# remote.net
KiCad netlist of a schematic drawn in EAGLE
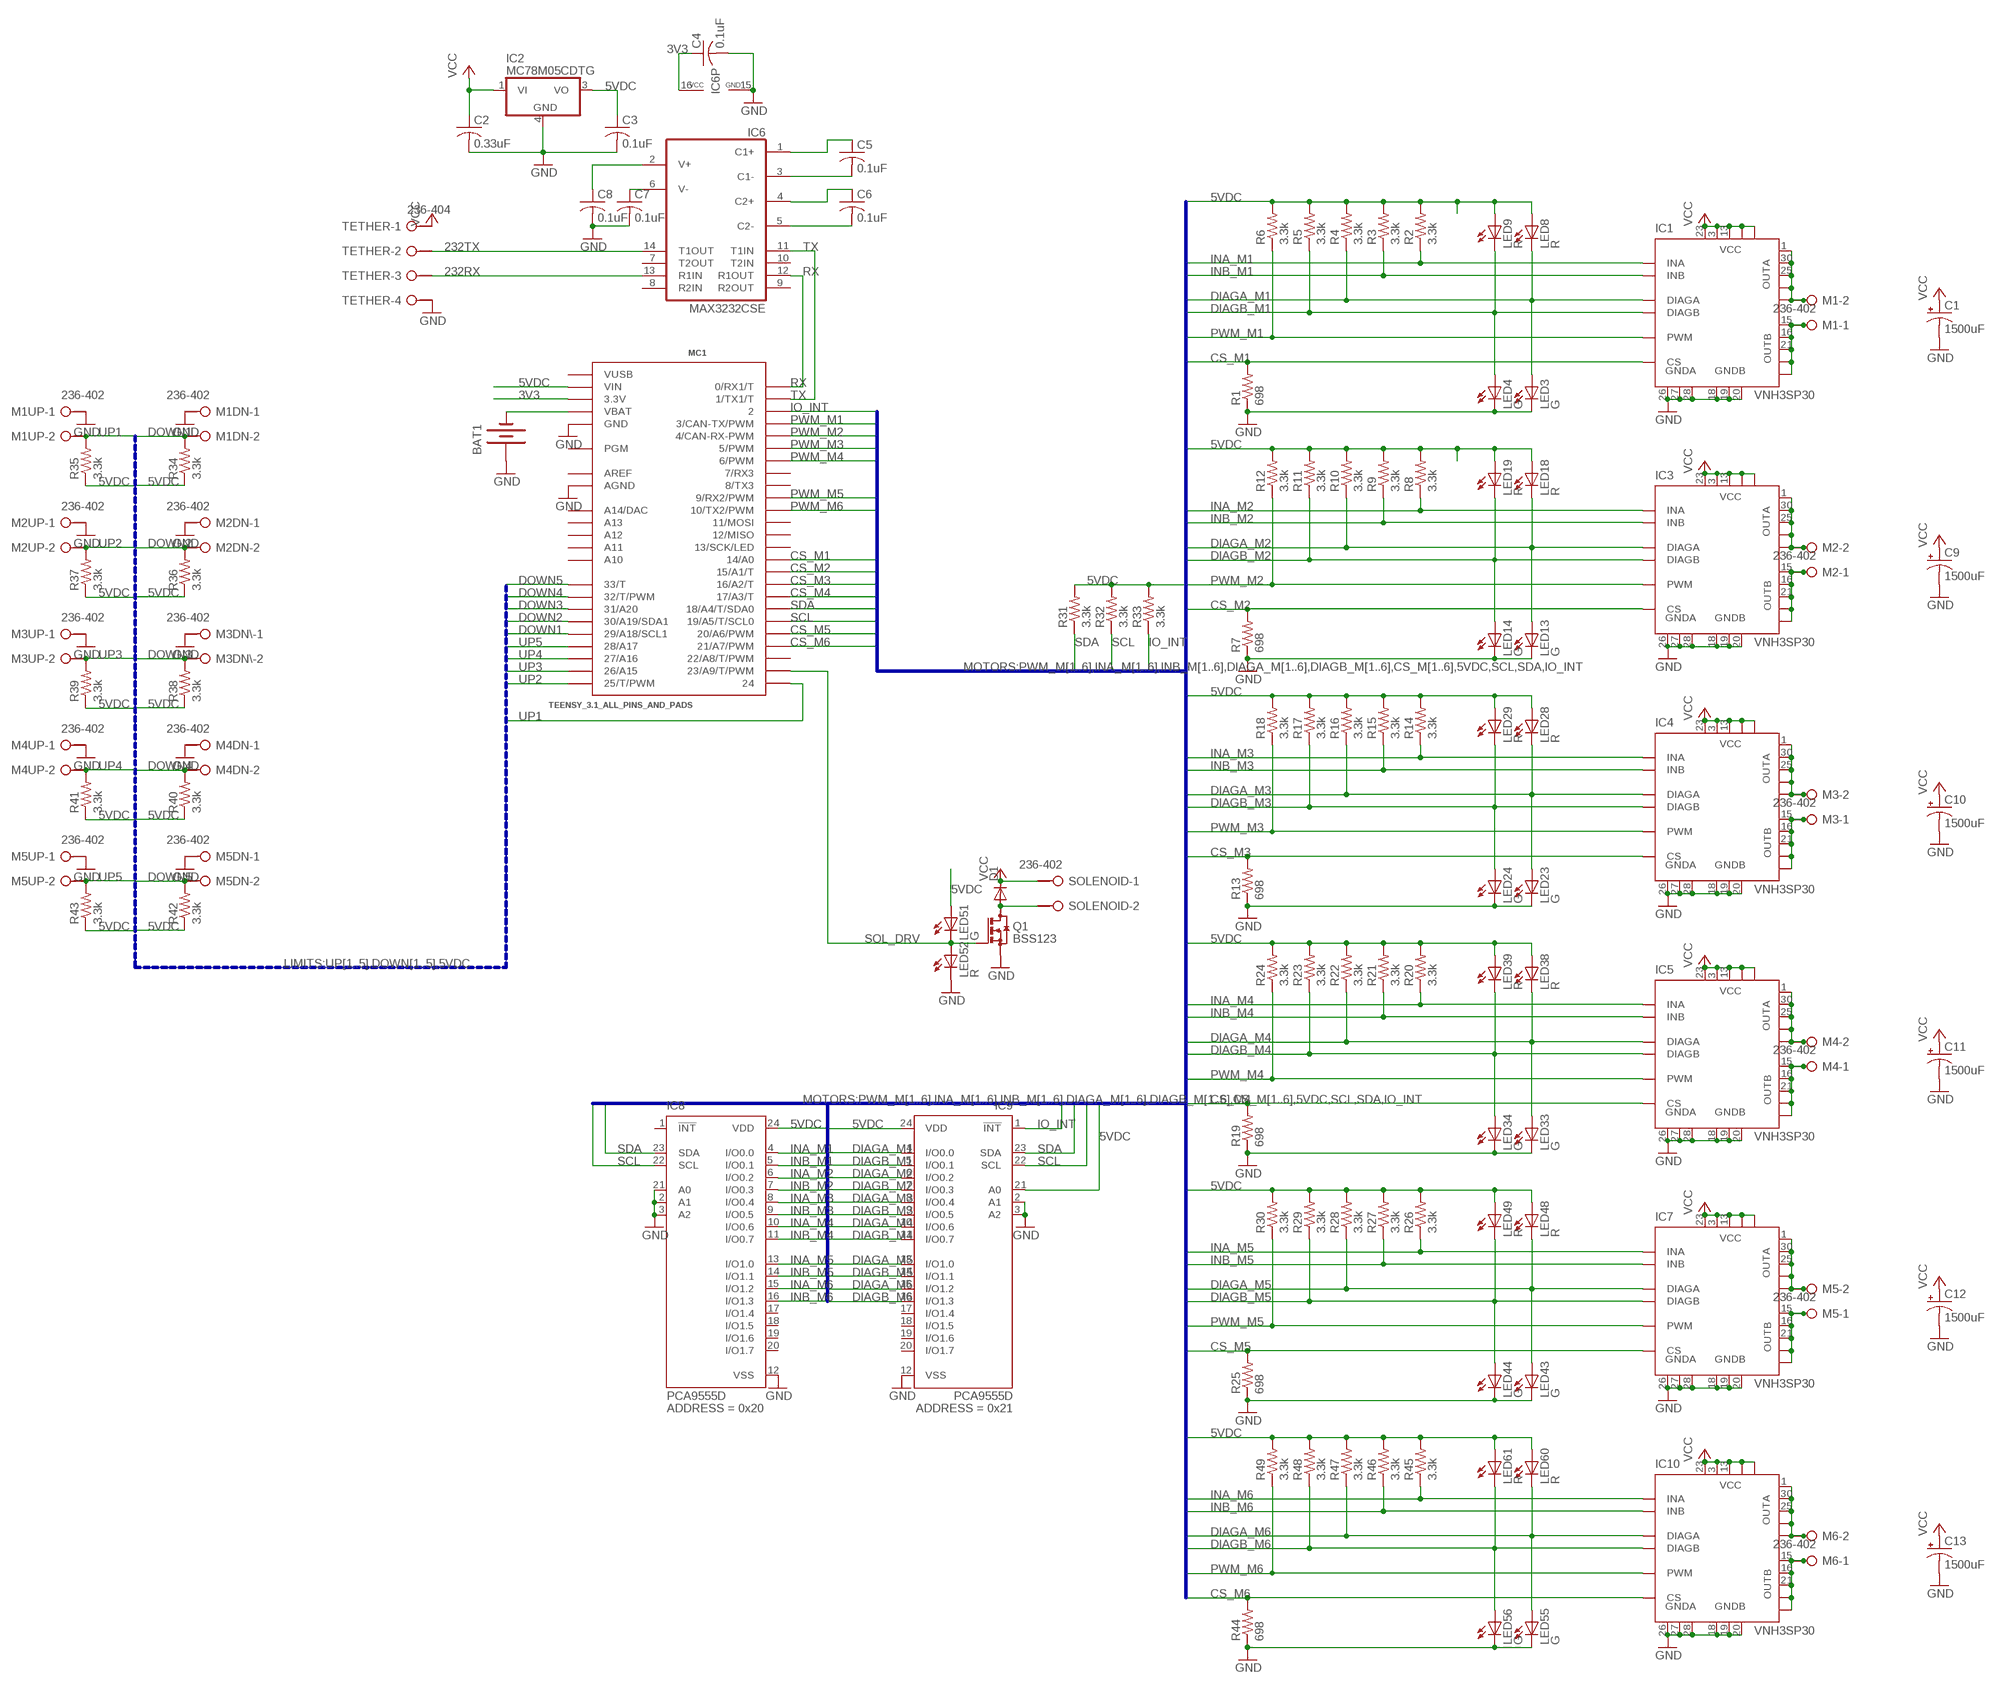
[diagram p0: schematic, sheet 1]

(export (version "E")
  (design (tool "Eeschema 10.0.6"))
  (components
    (comp (ref "BAT1")
      (value "BATTERY20SMD")
      (footprint "eagle-import:BATTCON_20MM")
      (libsource (lib "eagle-import") (part "BATTERY20SMD"))
    )
    (comp (ref "C1")
      (value "1500uF")
      (footprint "eagle-import:SANYO-OSCON_SMD_F12")
      (libsource (lib "eagle-import") (part "CPOL-USSANYO_SMD_F12"))
    )
    (comp (ref "C2")
      (value "0.33uF")
      (footprint "eagle-import:C0805")
      (libsource (lib "eagle-import") (part "C-USC0805"))
    )
    (comp (ref "C3")
      (value "0.1uF")
      (footprint "eagle-import:C0805")
      (libsource (lib "eagle-import") (part "C-USC0805"))
    )
    (comp (ref "C4")
      (value "0.1uF")
      (footprint "eagle-import:C0805")
      (libsource (lib "eagle-import") (part "C-USC0805"))
    )
    (comp (ref "C5")
      (value "0.1uF")
      (footprint "eagle-import:C0805")
      (libsource (lib "eagle-import") (part "C-USC0805"))
    )
    (comp (ref "C6")
      (value "0.1uF")
      (footprint "eagle-import:C0805")
      (libsource (lib "eagle-import") (part "C-USC0805"))
    )
    (comp (ref "C7")
      (value "0.1uF")
      (footprint "eagle-import:C0805")
      (libsource (lib "eagle-import") (part "C-USC0805"))
    )
    (comp (ref "C8")
      (value "0.1uF")
      (footprint "eagle-import:C0805")
      (libsource (lib "eagle-import") (part "C-USC0805"))
    )
    (comp (ref "C9")
      (value "1500uF")
      (footprint "eagle-import:SANYO-OSCON_SMD_F12")
      (libsource (lib "eagle-import") (part "CPOL-USSANYO_SMD_F12"))
    )
    (comp (ref "C10")
      (value "1500uF")
      (footprint "eagle-import:SANYO-OSCON_SMD_F12")
      (libsource (lib "eagle-import") (part "CPOL-USSANYO_SMD_F12"))
    )
    (comp (ref "C11")
      (value "1500uF")
      (footprint "eagle-import:SANYO-OSCON_SMD_F12")
      (libsource (lib "eagle-import") (part "CPOL-USSANYO_SMD_F12"))
    )
    (comp (ref "C12")
      (value "1500uF")
      (footprint "eagle-import:SANYO-OSCON_SMD_F12")
      (libsource (lib "eagle-import") (part "CPOL-USSANYO_SMD_F12"))
    )
    (comp (ref "C13")
      (value "1500uF")
      (footprint "eagle-import:SANYO-OSCON_SMD_F12")
      (libsource (lib "eagle-import") (part "CPOL-USSANYO_SMD_F12"))
    )
    (comp (ref "D1")
      (value "DIODE-DO214AA")
      (footprint "eagle-import:DO214AA")
      (libsource (lib "eagle-import") (part "DIODE-DO214AA"))
    )
    (comp (ref "IC1")
      (value "VNH3SP30")
      (footprint "eagle-import:MULTIPOWERSO-30")
      (fields (field (name "MPN") "VNH3SP30-E"))
      (libsource (lib "eagle-import") (part "VNH3SP30"))
    )
    (comp (ref "IC2")
      (value "MC78M05CDTG")
      (footprint "eagle-import:DPACK_3")
      (libsource (lib "eagle-import") (part "MC78M05CDTG"))
    )
    (comp (ref "IC3")
      (value "VNH3SP30")
      (footprint "eagle-import:MULTIPOWERSO-30")
      (fields (field (name "MPN") "VNH3SP30-E"))
      (libsource (lib "eagle-import") (part "VNH3SP30"))
    )
    (comp (ref "IC4")
      (value "VNH3SP30")
      (footprint "eagle-import:MULTIPOWERSO-30")
      (fields (field (name "MPN") "VNH3SP30-E"))
      (libsource (lib "eagle-import") (part "VNH3SP30"))
    )
    (comp (ref "IC5")
      (value "VNH3SP30")
      (footprint "eagle-import:MULTIPOWERSO-30")
      (fields (field (name "MPN") "VNH3SP30-E"))
      (libsource (lib "eagle-import") (part "VNH3SP30"))
    )
    (comp (ref "IC6")
      (value "MAX3232CSE")
      (footprint "eagle-import:SO16")
      (libsource (lib "eagle-import") (part "MAX3232SEC"))
    )
    (comp (ref "IC7")
      (value "VNH3SP30")
      (footprint "eagle-import:MULTIPOWERSO-30")
      (fields (field (name "MPN") "VNH3SP30-E"))
      (libsource (lib "eagle-import") (part "VNH3SP30"))
    )
    (comp (ref "IC8")
      (value "PCA9555D")
      (footprint "eagle-import:SO24")
      (fields (field (name "MPN") "PCA9555DW") (field (name "ADDRESS") "0x20"))
      (libsource (lib "eagle-import") (part "PCA9555D"))
    )
    (comp (ref "IC9")
      (value "PCA9555D")
      (footprint "eagle-import:SO24")
      (fields (field (name "MPN") "PCA9555DW") (field (name "ADDRESS") "0x21"))
      (libsource (lib "eagle-import") (part "PCA9555D"))
    )
    (comp (ref "IC10")
      (value "VNH3SP30")
      (footprint "eagle-import:MULTIPOWERSO-30")
      (fields (field (name "MPN") "VNH3SP30-E"))
      (libsource (lib "eagle-import") (part "VNH3SP30"))
    )
    (comp (ref "LED3")
      (value "G")
      (footprint "eagle-import:CHIP-LED0805")
      (libsource (lib "eagle-import") (part "LEDCHIP-LED0805"))
    )
    (comp (ref "LED4")
      (value "G")
      (footprint "eagle-import:CHIP-LED0805")
      (libsource (lib "eagle-import") (part "LEDCHIP-LED0805"))
    )
    (comp (ref "LED8")
      (value "R")
      (footprint "eagle-import:CHIP-LED0805")
      (libsource (lib "eagle-import") (part "LEDCHIP-LED0805"))
    )
    (comp (ref "LED9")
      (value "R")
      (footprint "eagle-import:CHIP-LED0805")
      (libsource (lib "eagle-import") (part "LEDCHIP-LED0805"))
    )
    (comp (ref "LED13")
      (value "G")
      (footprint "eagle-import:CHIP-LED0805")
      (libsource (lib "eagle-import") (part "LEDCHIP-LED0805"))
    )
    (comp (ref "LED14")
      (value "G")
      (footprint "eagle-import:CHIP-LED0805")
      (libsource (lib "eagle-import") (part "LEDCHIP-LED0805"))
    )
    (comp (ref "LED18")
      (value "R")
      (footprint "eagle-import:CHIP-LED0805")
      (libsource (lib "eagle-import") (part "LEDCHIP-LED0805"))
    )
    (comp (ref "LED19")
      (value "R")
      (footprint "eagle-import:CHIP-LED0805")
      (libsource (lib "eagle-import") (part "LEDCHIP-LED0805"))
    )
    (comp (ref "LED23")
      (value "G")
      (footprint "eagle-import:CHIP-LED0805")
      (libsource (lib "eagle-import") (part "LEDCHIP-LED0805"))
    )
    (comp (ref "LED24")
      (value "G")
      (footprint "eagle-import:CHIP-LED0805")
      (libsource (lib "eagle-import") (part "LEDCHIP-LED0805"))
    )
    (comp (ref "LED28")
      (value "R")
      (footprint "eagle-import:CHIP-LED0805")
      (libsource (lib "eagle-import") (part "LEDCHIP-LED0805"))
    )
    (comp (ref "LED29")
      (value "R")
      (footprint "eagle-import:CHIP-LED0805")
      (libsource (lib "eagle-import") (part "LEDCHIP-LED0805"))
    )
    (comp (ref "LED33")
      (value "G")
      (footprint "eagle-import:CHIP-LED0805")
      (libsource (lib "eagle-import") (part "LEDCHIP-LED0805"))
    )
    (comp (ref "LED34")
      (value "G")
      (footprint "eagle-import:CHIP-LED0805")
      (libsource (lib "eagle-import") (part "LEDCHIP-LED0805"))
    )
    (comp (ref "LED38")
      (value "R")
      (footprint "eagle-import:CHIP-LED0805")
      (libsource (lib "eagle-import") (part "LEDCHIP-LED0805"))
    )
    (comp (ref "LED39")
      (value "R")
      (footprint "eagle-import:CHIP-LED0805")
      (libsource (lib "eagle-import") (part "LEDCHIP-LED0805"))
    )
    (comp (ref "LED43")
      (value "G")
      (footprint "eagle-import:CHIP-LED0805")
      (libsource (lib "eagle-import") (part "LEDCHIP-LED0805"))
    )
    (comp (ref "LED44")
      (value "G")
      (footprint "eagle-import:CHIP-LED0805")
      (libsource (lib "eagle-import") (part "LEDCHIP-LED0805"))
    )
    (comp (ref "LED48")
      (value "R")
      (footprint "eagle-import:CHIP-LED0805")
      (libsource (lib "eagle-import") (part "LEDCHIP-LED0805"))
    )
    (comp (ref "LED49")
      (value "R")
      (footprint "eagle-import:CHIP-LED0805")
      (libsource (lib "eagle-import") (part "LEDCHIP-LED0805"))
    )
    (comp (ref "LED51")
      (value "G")
      (footprint "eagle-import:CHIP-LED0805")
      (libsource (lib "eagle-import") (part "LEDCHIP-LED0805"))
    )
    (comp (ref "LED52")
      (value "R")
      (footprint "eagle-import:CHIP-LED0805")
      (libsource (lib "eagle-import") (part "LEDCHIP-LED0805"))
    )
    (comp (ref "LED55")
      (value "G")
      (footprint "eagle-import:CHIP-LED0805")
      (libsource (lib "eagle-import") (part "LEDCHIP-LED0805"))
    )
    (comp (ref "LED56")
      (value "G")
      (footprint "eagle-import:CHIP-LED0805")
      (libsource (lib "eagle-import") (part "LEDCHIP-LED0805"))
    )
    (comp (ref "LED60")
      (value "R")
      (footprint "eagle-import:CHIP-LED0805")
      (libsource (lib "eagle-import") (part "LEDCHIP-LED0805"))
    )
    (comp (ref "LED61")
      (value "R")
      (footprint "eagle-import:CHIP-LED0805")
      (libsource (lib "eagle-import") (part "LEDCHIP-LED0805"))
    )
    (comp (ref "M1")
      (value "236-402")
      (footprint "eagle-import:236-402")
      (libsource (lib "eagle-import") (part "236-402"))
    )
    (comp (ref "M1DN")
      (value "236-402")
      (footprint "eagle-import:236-402")
      (libsource (lib "eagle-import") (part "236-402"))
    )
    (comp (ref "M1UP")
      (value "236-402")
      (footprint "eagle-import:236-402")
      (libsource (lib "eagle-import") (part "236-402"))
    )
    (comp (ref "M2")
      (value "236-402")
      (footprint "eagle-import:236-402")
      (libsource (lib "eagle-import") (part "236-402"))
    )
    (comp (ref "M2DN")
      (value "236-402")
      (footprint "eagle-import:236-402")
      (libsource (lib "eagle-import") (part "236-402"))
    )
    (comp (ref "M2UP")
      (value "236-402")
      (footprint "eagle-import:236-402")
      (libsource (lib "eagle-import") (part "236-402"))
    )
    (comp (ref "M3")
      (value "236-402")
      (footprint "eagle-import:236-402")
      (libsource (lib "eagle-import") (part "236-402"))
    )
    (comp (ref "M3DN\\")
      (value "236-402")
      (footprint "eagle-import:236-402")
      (libsource (lib "eagle-import") (part "236-402"))
    )
    (comp (ref "M3UP")
      (value "236-402")
      (footprint "eagle-import:236-402")
      (libsource (lib "eagle-import") (part "236-402"))
    )
    (comp (ref "M4")
      (value "236-402")
      (footprint "eagle-import:236-402")
      (libsource (lib "eagle-import") (part "236-402"))
    )
    (comp (ref "M4DN")
      (value "236-402")
      (footprint "eagle-import:236-402")
      (libsource (lib "eagle-import") (part "236-402"))
    )
    (comp (ref "M4UP")
      (value "236-402")
      (footprint "eagle-import:236-402")
      (libsource (lib "eagle-import") (part "236-402"))
    )
    (comp (ref "M5")
      (value "236-402")
      (footprint "eagle-import:236-402")
      (libsource (lib "eagle-import") (part "236-402"))
    )
    (comp (ref "M5DN")
      (value "236-402")
      (footprint "eagle-import:236-402")
      (libsource (lib "eagle-import") (part "236-402"))
    )
    (comp (ref "M5UP")
      (value "236-402")
      (footprint "eagle-import:236-402")
      (libsource (lib "eagle-import") (part "236-402"))
    )
    (comp (ref "M6")
      (value "236-402")
      (footprint "eagle-import:236-402")
      (libsource (lib "eagle-import") (part "236-402"))
    )
    (comp (ref "MC1")
      (value "TEENSY_3.1_ALL_PINS_AND_PADS")
      (footprint "eagle-import:TEENSY3_ALL_PINS_&_PADS")
      (libsource (lib "eagle-import") (part "TEENSY_3.1_ALL_PINS_AND_PADS"))
    )
    (comp (ref "Q1")
      (value "BSS123")
      (footprint "eagle-import:SOT23")
      (libsource (lib "eagle-import") (part "BSS123"))
    )
    (comp (ref "R1")
      (value "698")
      (footprint "eagle-import:R0805")
      (libsource (lib "eagle-import") (part "R-US_R0805"))
    )
    (comp (ref "R2")
      (value "3.3k")
      (footprint "eagle-import:R0805")
      (libsource (lib "eagle-import") (part "R-US_R0805"))
    )
    (comp (ref "R3")
      (value "3.3k")
      (footprint "eagle-import:R0805")
      (libsource (lib "eagle-import") (part "R-US_R0805"))
    )
    (comp (ref "R4")
      (value "3.3k")
      (footprint "eagle-import:R0805")
      (libsource (lib "eagle-import") (part "R-US_R0805"))
    )
    (comp (ref "R5")
      (value "3.3k")
      (footprint "eagle-import:R0805")
      (libsource (lib "eagle-import") (part "R-US_R0805"))
    )
    (comp (ref "R6")
      (value "3.3k")
      (footprint "eagle-import:R0805")
      (libsource (lib "eagle-import") (part "R-US_R0805"))
    )
    (comp (ref "R7")
      (value "698")
      (footprint "eagle-import:R0805")
      (libsource (lib "eagle-import") (part "R-US_R0805"))
    )
    (comp (ref "R8")
      (value "3.3k")
      (footprint "eagle-import:R0805")
      (libsource (lib "eagle-import") (part "R-US_R0805"))
    )
    (comp (ref "R9")
      (value "3.3k")
      (footprint "eagle-import:R0805")
      (libsource (lib "eagle-import") (part "R-US_R0805"))
    )
    (comp (ref "R10")
      (value "3.3k")
      (footprint "eagle-import:R0805")
      (libsource (lib "eagle-import") (part "R-US_R0805"))
    )
    (comp (ref "R11")
      (value "3.3k")
      (footprint "eagle-import:R0805")
      (libsource (lib "eagle-import") (part "R-US_R0805"))
    )
    (comp (ref "R12")
      (value "3.3k")
      (footprint "eagle-import:R0805")
      (libsource (lib "eagle-import") (part "R-US_R0805"))
    )
    (comp (ref "R13")
      (value "698")
      (footprint "eagle-import:R0805")
      (libsource (lib "eagle-import") (part "R-US_R0805"))
    )
    (comp (ref "R14")
      (value "3.3k")
      (footprint "eagle-import:R0805")
      (libsource (lib "eagle-import") (part "R-US_R0805"))
    )
    (comp (ref "R15")
      (value "3.3k")
      (footprint "eagle-import:R0805")
      (libsource (lib "eagle-import") (part "R-US_R0805"))
    )
    (comp (ref "R16")
      (value "3.3k")
      (footprint "eagle-import:R0805")
      (libsource (lib "eagle-import") (part "R-US_R0805"))
    )
    (comp (ref "R17")
      (value "3.3k")
      (footprint "eagle-import:R0805")
      (libsource (lib "eagle-import") (part "R-US_R0805"))
    )
    (comp (ref "R18")
      (value "3.3k")
      (footprint "eagle-import:R0805")
      (libsource (lib "eagle-import") (part "R-US_R0805"))
    )
    (comp (ref "R19")
      (value "698")
      (footprint "eagle-import:R0805")
      (libsource (lib "eagle-import") (part "R-US_R0805"))
    )
    (comp (ref "R20")
      (value "3.3k")
      (footprint "eagle-import:R0805")
      (libsource (lib "eagle-import") (part "R-US_R0805"))
    )
    (comp (ref "R21")
      (value "3.3k")
      (footprint "eagle-import:R0805")
      (libsource (lib "eagle-import") (part "R-US_R0805"))
    )
    (comp (ref "R22")
      (value "3.3k")
      (footprint "eagle-import:R0805")
      (libsource (lib "eagle-import") (part "R-US_R0805"))
    )
    (comp (ref "R23")
      (value "3.3k")
      (footprint "eagle-import:R0805")
      (libsource (lib "eagle-import") (part "R-US_R0805"))
    )
    (comp (ref "R24")
      (value "3.3k")
      (footprint "eagle-import:R0805")
      (libsource (lib "eagle-import") (part "R-US_R0805"))
    )
    (comp (ref "R25")
      (value "698")
      (footprint "eagle-import:R0805")
      (libsource (lib "eagle-import") (part "R-US_R0805"))
    )
    (comp (ref "R26")
      (value "3.3k")
      (footprint "eagle-import:R0805")
      (libsource (lib "eagle-import") (part "R-US_R0805"))
    )
    (comp (ref "R27")
      (value "3.3k")
      (footprint "eagle-import:R0805")
      (libsource (lib "eagle-import") (part "R-US_R0805"))
    )
    (comp (ref "R28")
      (value "3.3k")
      (footprint "eagle-import:R0805")
      (libsource (lib "eagle-import") (part "R-US_R0805"))
    )
    (comp (ref "R29")
      (value "3.3k")
      (footprint "eagle-import:R0805")
      (libsource (lib "eagle-import") (part "R-US_R0805"))
    )
    (comp (ref "R30")
      (value "3.3k")
      (footprint "eagle-import:R0805")
      (libsource (lib "eagle-import") (part "R-US_R0805"))
    )
    (comp (ref "R31")
      (value "3.3k")
      (footprint "eagle-import:R0805")
      (libsource (lib "eagle-import") (part "R-US_R0805"))
    )
    (comp (ref "R32")
      (value "3.3k")
      (footprint "eagle-import:R0805")
      (libsource (lib "eagle-import") (part "R-US_R0805"))
    )
    (comp (ref "R33")
      (value "3.3k")
      (footprint "eagle-import:R0805")
      (libsource (lib "eagle-import") (part "R-US_R0805"))
    )
    (comp (ref "R34")
      (value "3.3k")
      (footprint "eagle-import:R0805")
      (libsource (lib "eagle-import") (part "R-US_R0805"))
    )
    (comp (ref "R35")
      (value "3.3k")
      (footprint "eagle-import:R0805")
      (libsource (lib "eagle-import") (part "R-US_R0805"))
    )
    (comp (ref "R36")
      (value "3.3k")
      (footprint "eagle-import:R0805")
      (libsource (lib "eagle-import") (part "R-US_R0805"))
    )
    (comp (ref "R37")
      (value "3.3k")
      (footprint "eagle-import:R0805")
      (libsource (lib "eagle-import") (part "R-US_R0805"))
    )
    (comp (ref "R38")
      (value "3.3k")
      (footprint "eagle-import:R0805")
      (libsource (lib "eagle-import") (part "R-US_R0805"))
    )
    (comp (ref "R39")
      (value "3.3k")
      (footprint "eagle-import:R0805")
      (libsource (lib "eagle-import") (part "R-US_R0805"))
    )
    (comp (ref "R40")
      (value "3.3k")
      (footprint "eagle-import:R0805")
      (libsource (lib "eagle-import") (part "R-US_R0805"))
    )
    (comp (ref "R41")
      (value "3.3k")
      (footprint "eagle-import:R0805")
      (libsource (lib "eagle-import") (part "R-US_R0805"))
    )
    (comp (ref "R42")
      (value "3.3k")
      (footprint "eagle-import:R0805")
      (libsource (lib "eagle-import") (part "R-US_R0805"))
    )
    (comp (ref "R43")
      (value "3.3k")
      (footprint "eagle-import:R0805")
      (libsource (lib "eagle-import") (part "R-US_R0805"))
    )
    (comp (ref "R44")
      (value "698")
      (footprint "eagle-import:R0805")
      (libsource (lib "eagle-import") (part "R-US_R0805"))
    )
    (comp (ref "R45")
      (value "3.3k")
      (footprint "eagle-import:R0805")
      (libsource (lib "eagle-import") (part "R-US_R0805"))
    )
    (comp (ref "R46")
      (value "3.3k")
      (footprint "eagle-import:R0805")
      (libsource (lib "eagle-import") (part "R-US_R0805"))
    )
    (comp (ref "R47")
      (value "3.3k")
      (footprint "eagle-import:R0805")
      (libsource (lib "eagle-import") (part "R-US_R0805"))
    )
    (comp (ref "R48")
      (value "3.3k")
      (footprint "eagle-import:R0805")
      (libsource (lib "eagle-import") (part "R-US_R0805"))
    )
    (comp (ref "R49")
      (value "3.3k")
      (footprint "eagle-import:R0805")
      (libsource (lib "eagle-import") (part "R-US_R0805"))
    )
    (comp (ref "SOLENOID")
      (value "236-402")
      (footprint "eagle-import:236-402")
      (libsource (lib "eagle-import") (part "236-402"))
    )
    (comp (ref "TETHER")
      (value "236-404")
      (footprint "eagle-import:236-404")
      (libsource (lib "eagle-import") (part "236-404"))
    )
  )
  (nets
    (net (code "1") (name "/3V3") (class "Default")
      (node (ref "C4") (pin "1") (pinfunction "1_1") (pintype "passive"))
      (node (ref "IC6") (pin "16") (pinfunction "VCC_16") (pintype "power_in"))
      (node (ref "MC1") (pin "3.3V") (pinfunction "3.3V_3.3V") (pintype "power_in"))
      (node (ref "MC1") (pin "3.3V1") (pinfunction "3.3V_3.3V1") (pintype "power_in"))
      (node (ref "MC1") (pin "3.3V2") (pinfunction "3.3V_3.3V2") (pintype "power_in"))
    )
    (net (code "2") (name "/5VDC") (class "Default")
      (node (ref "C3") (pin "1") (pinfunction "1_1") (pintype "passive"))
      (node (ref "IC2") (pin "3") (pinfunction "VO_3") (pintype "passive"))
      (node (ref "IC8") (pin "24") (pinfunction "VDD_24") (pintype "power_in"))
      (node (ref "IC9") (pin "21") (pinfunction "A0_21") (pintype "input"))
      (node (ref "IC9") (pin "24") (pinfunction "VDD_24") (pintype "power_in"))
      (node (ref "LED18") (pin "A") (pinfunction "A_A") (pintype "passive"))
      (node (ref "LED19") (pin "A") (pinfunction "A_A") (pintype "passive"))
      (node (ref "LED28") (pin "A") (pinfunction "A_A") (pintype "passive"))
      (node (ref "LED29") (pin "A") (pinfunction "A_A") (pintype "passive"))
      (node (ref "LED38") (pin "A") (pinfunction "A_A") (pintype "passive"))
      (node (ref "LED39") (pin "A") (pinfunction "A_A") (pintype "passive"))
      (node (ref "LED48") (pin "A") (pinfunction "A_A") (pintype "passive"))
      (node (ref "LED49") (pin "A") (pinfunction "A_A") (pintype "passive"))
      (node (ref "LED51") (pin "A") (pinfunction "A_A") (pintype "passive"))
      (node (ref "LED60") (pin "A") (pinfunction "A_A") (pintype "passive"))
      (node (ref "LED61") (pin "A") (pinfunction "A_A") (pintype "passive"))
      (node (ref "LED8") (pin "A") (pinfunction "A_A") (pintype "passive"))
      (node (ref "LED9") (pin "A") (pinfunction "A_A") (pintype "passive"))
      (node (ref "MC1") (pin "VIN") (pinfunction "VIN_VIN") (pintype "power_in"))
      (node (ref "R10") (pin "2") (pinfunction "2_2") (pintype "passive"))
      (node (ref "R11") (pin "2") (pinfunction "2_2") (pintype "passive"))
      (node (ref "R12") (pin "2") (pinfunction "2_2") (pintype "passive"))
      (node (ref "R14") (pin "2") (pinfunction "2_2") (pintype "passive"))
      (node (ref "R15") (pin "2") (pinfunction "2_2") (pintype "passive"))
      (node (ref "R16") (pin "2") (pinfunction "2_2") (pintype "passive"))
      (node (ref "R17") (pin "2") (pinfunction "2_2") (pintype "passive"))
      (node (ref "R18") (pin "2") (pinfunction "2_2") (pintype "passive"))
      (node (ref "R2") (pin "2") (pinfunction "2_2") (pintype "passive"))
      (node (ref "R20") (pin "2") (pinfunction "2_2") (pintype "passive"))
      (node (ref "R21") (pin "2") (pinfunction "2_2") (pintype "passive"))
      (node (ref "R22") (pin "2") (pinfunction "2_2") (pintype "passive"))
      (node (ref "R23") (pin "2") (pinfunction "2_2") (pintype "passive"))
      (node (ref "R24") (pin "2") (pinfunction "2_2") (pintype "passive"))
      (node (ref "R26") (pin "2") (pinfunction "2_2") (pintype "passive"))
      (node (ref "R27") (pin "2") (pinfunction "2_2") (pintype "passive"))
      (node (ref "R28") (pin "2") (pinfunction "2_2") (pintype "passive"))
      (node (ref "R29") (pin "2") (pinfunction "2_2") (pintype "passive"))
      (node (ref "R3") (pin "2") (pinfunction "2_2") (pintype "passive"))
      (node (ref "R30") (pin "2") (pinfunction "2_2") (pintype "passive"))
      (node (ref "R31") (pin "2") (pinfunction "2_2") (pintype "passive"))
      (node (ref "R32") (pin "2") (pinfunction "2_2") (pintype "passive"))
      (node (ref "R33") (pin "2") (pinfunction "2_2") (pintype "passive"))
      (node (ref "R34") (pin "1") (pinfunction "1_1") (pintype "passive"))
      (node (ref "R35") (pin "1") (pinfunction "1_1") (pintype "passive"))
      (node (ref "R36") (pin "1") (pinfunction "1_1") (pintype "passive"))
      (node (ref "R37") (pin "1") (pinfunction "1_1") (pintype "passive"))
      (node (ref "R38") (pin "1") (pinfunction "1_1") (pintype "passive"))
      (node (ref "R39") (pin "1") (pinfunction "1_1") (pintype "passive"))
      (node (ref "R4") (pin "2") (pinfunction "2_2") (pintype "passive"))
      (node (ref "R40") (pin "1") (pinfunction "1_1") (pintype "passive"))
      (node (ref "R41") (pin "1") (pinfunction "1_1") (pintype "passive"))
      (node (ref "R42") (pin "1") (pinfunction "1_1") (pintype "passive"))
      (node (ref "R43") (pin "1") (pinfunction "1_1") (pintype "passive"))
      (node (ref "R45") (pin "2") (pinfunction "2_2") (pintype "passive"))
      (node (ref "R46") (pin "2") (pinfunction "2_2") (pintype "passive"))
      (node (ref "R47") (pin "2") (pinfunction "2_2") (pintype "passive"))
      (node (ref "R48") (pin "2") (pinfunction "2_2") (pintype "passive"))
      (node (ref "R49") (pin "2") (pinfunction "2_2") (pintype "passive"))
      (node (ref "R5") (pin "2") (pinfunction "2_2") (pintype "passive"))
      (node (ref "R6") (pin "2") (pinfunction "2_2") (pintype "passive"))
      (node (ref "R8") (pin "2") (pinfunction "2_2") (pintype "passive"))
      (node (ref "R9") (pin "2") (pinfunction "2_2") (pintype "passive"))
    )
    (net (code "3") (name "/232RX") (class "Default")
      (node (ref "IC6") (pin "13") (pinfunction "R1IN_13") (pintype "input"))
      (node (ref "TETHER") (pin "3@1") (pinfunction "KL1_3@1") (pintype "passive"))
    )
    (net (code "4") (name "/232TX") (class "Default")
      (node (ref "IC6") (pin "14") (pinfunction "T1OUT_14") (pintype "output"))
      (node (ref "TETHER") (pin "2@1") (pinfunction "KL1_2@1") (pintype "passive"))
    )
    (net (code "5") (name "/AREF") (class "Default")
      (node (ref "MC1") (pin "AREF") (pinfunction "AREF_AREF") (pintype "power_in"))
    )
    (net (code "6") (name "/CS_M1") (class "Default")
      (node (ref "IC1") (pin "9") (pinfunction "CS_9") (pintype "output"))
      (node (ref "MC1") (pin "14/A0") (pinfunction "14/A0_14/A0") (pintype "bidirectional"))
      (node (ref "R1") (pin "2") (pinfunction "2_2") (pintype "passive"))
    )
    (net (code "7") (name "/CS_M2") (class "Default")
      (node (ref "IC3") (pin "9") (pinfunction "CS_9") (pintype "output"))
      (node (ref "MC1") (pin "15/A1") (pinfunction "15/A1/T_15/A1") (pintype "bidirectional"))
      (node (ref "R7") (pin "2") (pinfunction "2_2") (pintype "passive"))
    )
    (net (code "8") (name "/CS_M3") (class "Default")
      (node (ref "IC4") (pin "9") (pinfunction "CS_9") (pintype "output"))
      (node (ref "MC1") (pin "16/A2") (pinfunction "16/A2/T_16/A2") (pintype "bidirectional"))
      (node (ref "R13") (pin "2") (pinfunction "2_2") (pintype "passive"))
    )
    (net (code "9") (name "/CS_M4") (class "Default")
      (node (ref "IC5") (pin "9") (pinfunction "CS_9") (pintype "output"))
      (node (ref "MC1") (pin "17/A3") (pinfunction "17/A3/T_17/A3") (pintype "bidirectional"))
      (node (ref "R19") (pin "2") (pinfunction "2_2") (pintype "passive"))
    )
    (net (code "10") (name "/CS_M5") (class "Default")
      (node (ref "IC7") (pin "9") (pinfunction "CS_9") (pintype "output"))
      (node (ref "MC1") (pin "20/A6") (pinfunction "20/A6/PWM_20/A6") (pintype "bidirectional"))
      (node (ref "R25") (pin "2") (pinfunction "2_2") (pintype "passive"))
    )
    (net (code "11") (name "/CS_M6") (class "Default")
      (node (ref "IC10") (pin "9") (pinfunction "CS_9") (pintype "output"))
      (node (ref "MC1") (pin "21/A7") (pinfunction "21/A7/PWM_21/A7") (pintype "bidirectional"))
      (node (ref "R44") (pin "2") (pinfunction "2_2") (pintype "passive"))
    )
    (net (code "12") (name "/DIAGA_M1") (class "Default")
      (node (ref "IC1") (pin "6") (pinfunction "DIAGA_6") (pintype "open_collector"))
      (node (ref "IC9") (pin "4") (pinfunction "I/O0.0_4") (pintype "bidirectional"))
      (node (ref "LED3") (pin "A") (pinfunction "A_A") (pintype "passive"))
      (node (ref "LED8") (pin "C") (pinfunction "C_C") (pintype "passive"))
      (node (ref "R4") (pin "1") (pinfunction "1_1") (pintype "passive"))
    )
    (net (code "13") (name "/DIAGA_M2") (class "Default")
      (node (ref "IC3") (pin "6") (pinfunction "DIAGA_6") (pintype "open_collector"))
      (node (ref "IC9") (pin "6") (pinfunction "I/O0.2_6") (pintype "bidirectional"))
      (node (ref "LED13") (pin "A") (pinfunction "A_A") (pintype "passive"))
      (node (ref "LED18") (pin "C") (pinfunction "C_C") (pintype "passive"))
      (node (ref "R10") (pin "1") (pinfunction "1_1") (pintype "passive"))
    )
    (net (code "14") (name "/DIAGA_M3") (class "Default")
      (node (ref "IC4") (pin "6") (pinfunction "DIAGA_6") (pintype "open_collector"))
      (node (ref "IC9") (pin "8") (pinfunction "I/O0.4_8") (pintype "bidirectional"))
      (node (ref "LED23") (pin "A") (pinfunction "A_A") (pintype "passive"))
      (node (ref "LED28") (pin "C") (pinfunction "C_C") (pintype "passive"))
      (node (ref "R16") (pin "1") (pinfunction "1_1") (pintype "passive"))
    )
    (net (code "15") (name "/DIAGA_M4") (class "Default")
      (node (ref "IC5") (pin "6") (pinfunction "DIAGA_6") (pintype "open_collector"))
      (node (ref "IC9") (pin "10") (pinfunction "I/O0.6_10") (pintype "bidirectional"))
      (node (ref "LED33") (pin "A") (pinfunction "A_A") (pintype "passive"))
      (node (ref "LED38") (pin "C") (pinfunction "C_C") (pintype "passive"))
      (node (ref "R22") (pin "1") (pinfunction "1_1") (pintype "passive"))
    )
    (net (code "16") (name "/DIAGA_M5") (class "Default")
      (node (ref "IC7") (pin "6") (pinfunction "DIAGA_6") (pintype "open_collector"))
      (node (ref "IC9") (pin "13") (pinfunction "I/O1.0_13") (pintype "bidirectional"))
      (node (ref "LED43") (pin "A") (pinfunction "A_A") (pintype "passive"))
      (node (ref "LED48") (pin "C") (pinfunction "C_C") (pintype "passive"))
      (node (ref "R28") (pin "1") (pinfunction "1_1") (pintype "passive"))
    )
    (net (code "17") (name "/DIAGA_M6") (class "Default")
      (node (ref "IC10") (pin "6") (pinfunction "DIAGA_6") (pintype "open_collector"))
      (node (ref "IC9") (pin "15") (pinfunction "I/O1.2_15") (pintype "bidirectional"))
      (node (ref "LED55") (pin "A") (pinfunction "A_A") (pintype "passive"))
      (node (ref "LED60") (pin "C") (pinfunction "C_C") (pintype "passive"))
      (node (ref "R47") (pin "1") (pinfunction "1_1") (pintype "passive"))
    )
    (net (code "18") (name "/DIAGB_M1") (class "Default")
      (node (ref "IC1") (pin "10") (pinfunction "DIAGB_10") (pintype "open_collector"))
      (node (ref "IC9") (pin "5") (pinfunction "I/O0.1_5") (pintype "bidirectional"))
      (node (ref "LED4") (pin "A") (pinfunction "A_A") (pintype "passive"))
      (node (ref "LED9") (pin "C") (pinfunction "C_C") (pintype "passive"))
      (node (ref "R5") (pin "1") (pinfunction "1_1") (pintype "passive"))
    )
    (net (code "19") (name "/DIAGB_M2") (class "Default")
      (node (ref "IC3") (pin "10") (pinfunction "DIAGB_10") (pintype "open_collector"))
      (node (ref "IC9") (pin "7") (pinfunction "I/O0.3_7") (pintype "bidirectional"))
      (node (ref "LED14") (pin "A") (pinfunction "A_A") (pintype "passive"))
      (node (ref "LED19") (pin "C") (pinfunction "C_C") (pintype "passive"))
      (node (ref "R11") (pin "1") (pinfunction "1_1") (pintype "passive"))
    )
    (net (code "20") (name "/DIAGB_M3") (class "Default")
      (node (ref "IC4") (pin "10") (pinfunction "DIAGB_10") (pintype "open_collector"))
      (node (ref "IC9") (pin "9") (pinfunction "I/O0.5_9") (pintype "bidirectional"))
      (node (ref "LED24") (pin "A") (pinfunction "A_A") (pintype "passive"))
      (node (ref "LED29") (pin "C") (pinfunction "C_C") (pintype "passive"))
      (node (ref "R17") (pin "1") (pinfunction "1_1") (pintype "passive"))
    )
    (net (code "21") (name "/DIAGB_M4") (class "Default")
      (node (ref "IC5") (pin "10") (pinfunction "DIAGB_10") (pintype "open_collector"))
      (node (ref "IC9") (pin "11") (pinfunction "I/O0.7_11") (pintype "bidirectional"))
      (node (ref "LED34") (pin "A") (pinfunction "A_A") (pintype "passive"))
      (node (ref "LED39") (pin "C") (pinfunction "C_C") (pintype "passive"))
      (node (ref "R23") (pin "1") (pinfunction "1_1") (pintype "passive"))
    )
    (net (code "22") (name "/DIAGB_M5") (class "Default")
      (node (ref "IC7") (pin "10") (pinfunction "DIAGB_10") (pintype "open_collector"))
      (node (ref "IC9") (pin "14") (pinfunction "I/O1.1_14") (pintype "bidirectional"))
      (node (ref "LED44") (pin "A") (pinfunction "A_A") (pintype "passive"))
      (node (ref "LED49") (pin "C") (pinfunction "C_C") (pintype "passive"))
      (node (ref "R29") (pin "1") (pinfunction "1_1") (pintype "passive"))
    )
    (net (code "23") (name "/DIAGB_M6") (class "Default")
      (node (ref "IC10") (pin "10") (pinfunction "DIAGB_10") (pintype "open_collector"))
      (node (ref "IC9") (pin "16") (pinfunction "I/O1.3_16") (pintype "bidirectional"))
      (node (ref "LED56") (pin "A") (pinfunction "A_A") (pintype "passive"))
      (node (ref "LED61") (pin "C") (pinfunction "C_C") (pintype "passive"))
      (node (ref "R48") (pin "1") (pinfunction "1_1") (pintype "passive"))
    )
    (net (code "24") (name "/DOWN1") (class "Default")
      (node (ref "M1DN") (pin "2@1") (pinfunction "KL1_2@1") (pintype "passive"))
      (node (ref "MC1") (pin "29") (pinfunction "29/A18/SCL1_29") (pintype "bidirectional"))
      (node (ref "R34") (pin "2") (pinfunction "2_2") (pintype "passive"))
    )
    (net (code "25") (name "/DOWN2") (class "Default")
      (node (ref "M2DN") (pin "2@1") (pinfunction "KL1_2@1") (pintype "passive"))
      (node (ref "MC1") (pin "30") (pinfunction "30/A19/SDA1_30") (pintype "bidirectional"))
      (node (ref "R36") (pin "2") (pinfunction "2_2") (pintype "passive"))
    )
    (net (code "26") (name "/DOWN3") (class "Default")
      (node (ref "M3DN\\") (pin "2@1") (pinfunction "KL1_2@1") (pintype "passive"))
      (node (ref "MC1") (pin "31") (pinfunction "31/A20_31") (pintype "bidirectional"))
      (node (ref "R38") (pin "2") (pinfunction "2_2") (pintype "passive"))
    )
    (net (code "27") (name "/DOWN4") (class "Default")
      (node (ref "M4DN") (pin "2@1") (pinfunction "KL1_2@1") (pintype "passive"))
      (node (ref "MC1") (pin "32") (pinfunction "32/T/PWM_32") (pintype "bidirectional"))
      (node (ref "R40") (pin "2") (pinfunction "2_2") (pintype "passive"))
    )
    (net (code "28") (name "/DOWN5") (class "Default")
      (node (ref "M5DN") (pin "2@1") (pinfunction "KL1_2@1") (pintype "passive"))
      (node (ref "MC1") (pin "33") (pinfunction "33/T_33") (pintype "bidirectional"))
      (node (ref "R42") (pin "2") (pinfunction "2_2") (pintype "passive"))
    )
    (net (code "29") (name "/INA_M1") (class "Default")
      (node (ref "IC1") (pin "5") (pinfunction "INA_5") (pintype "input"))
      (node (ref "IC8") (pin "4") (pinfunction "I/O0.0_4") (pintype "bidirectional"))
      (node (ref "R2") (pin "1") (pinfunction "1_1") (pintype "passive"))
    )
    (net (code "30") (name "/INA_M2") (class "Default")
      (node (ref "IC3") (pin "5") (pinfunction "INA_5") (pintype "input"))
      (node (ref "IC8") (pin "6") (pinfunction "I/O0.2_6") (pintype "bidirectional"))
      (node (ref "R8") (pin "1") (pinfunction "1_1") (pintype "passive"))
    )
    (net (code "31") (name "/INA_M3") (class "Default")
      (node (ref "IC4") (pin "5") (pinfunction "INA_5") (pintype "input"))
      (node (ref "IC8") (pin "8") (pinfunction "I/O0.4_8") (pintype "bidirectional"))
      (node (ref "R14") (pin "1") (pinfunction "1_1") (pintype "passive"))
    )
    (net (code "32") (name "/INA_M4") (class "Default")
      (node (ref "IC5") (pin "5") (pinfunction "INA_5") (pintype "input"))
      (node (ref "IC8") (pin "10") (pinfunction "I/O0.6_10") (pintype "bidirectional"))
      (node (ref "R20") (pin "1") (pinfunction "1_1") (pintype "passive"))
    )
    (net (code "33") (name "/INA_M5") (class "Default")
      (node (ref "IC7") (pin "5") (pinfunction "INA_5") (pintype "input"))
      (node (ref "IC8") (pin "13") (pinfunction "I/O1.0_13") (pintype "bidirectional"))
      (node (ref "R26") (pin "1") (pinfunction "1_1") (pintype "passive"))
    )
    (net (code "34") (name "/INA_M6") (class "Default")
      (node (ref "IC10") (pin "5") (pinfunction "INA_5") (pintype "input"))
      (node (ref "IC8") (pin "15") (pinfunction "I/O1.2_15") (pintype "bidirectional"))
      (node (ref "R45") (pin "1") (pinfunction "1_1") (pintype "passive"))
    )
    (net (code "35") (name "/INB_M1") (class "Default")
      (node (ref "IC1") (pin "11") (pinfunction "INB_11") (pintype "input"))
      (node (ref "IC8") (pin "5") (pinfunction "I/O0.1_5") (pintype "bidirectional"))
      (node (ref "R3") (pin "1") (pinfunction "1_1") (pintype "passive"))
    )
    (net (code "36") (name "/INB_M2") (class "Default")
      (node (ref "IC3") (pin "11") (pinfunction "INB_11") (pintype "input"))
      (node (ref "IC8") (pin "7") (pinfunction "I/O0.3_7") (pintype "bidirectional"))
      (node (ref "R9") (pin "1") (pinfunction "1_1") (pintype "passive"))
    )
    (net (code "37") (name "/INB_M3") (class "Default")
      (node (ref "IC4") (pin "11") (pinfunction "INB_11") (pintype "input"))
      (node (ref "IC8") (pin "9") (pinfunction "I/O0.5_9") (pintype "bidirectional"))
      (node (ref "R15") (pin "1") (pinfunction "1_1") (pintype "passive"))
    )
    (net (code "38") (name "/INB_M4") (class "Default")
      (node (ref "IC5") (pin "11") (pinfunction "INB_11") (pintype "input"))
      (node (ref "IC8") (pin "11") (pinfunction "I/O0.7_11") (pintype "bidirectional"))
      (node (ref "R21") (pin "1") (pinfunction "1_1") (pintype "passive"))
    )
    (net (code "39") (name "/INB_M5") (class "Default")
      (node (ref "IC7") (pin "11") (pinfunction "INB_11") (pintype "input"))
      (node (ref "IC8") (pin "14") (pinfunction "I/O1.1_14") (pintype "bidirectional"))
      (node (ref "R27") (pin "1") (pinfunction "1_1") (pintype "passive"))
    )
    (net (code "40") (name "/INB_M6") (class "Default")
      (node (ref "IC10") (pin "11") (pinfunction "INB_11") (pintype "input"))
      (node (ref "IC8") (pin "16") (pinfunction "I/O1.3_16") (pintype "bidirectional"))
      (node (ref "R46") (pin "1") (pinfunction "1_1") (pintype "passive"))
    )
    (net (code "41") (name "/IO_INT") (class "Default")
      (node (ref "IC9") (pin "1") (pinfunction "~{INT}_1") (pintype "output"))
      (node (ref "MC1") (pin "2") (pinfunction "2_2") (pintype "bidirectional"))
      (node (ref "R33") (pin "1") (pinfunction "1_1") (pintype "passive"))
    )
    (net (code "42") (name "/PWM_M1") (class "Default")
      (node (ref "IC1") (pin "8") (pinfunction "PWM_8") (pintype "input"))
      (node (ref "MC1") (pin "3") (pinfunction "3/CAN-TX/PWM_3") (pintype "bidirectional"))
      (node (ref "R6") (pin "1") (pinfunction "1_1") (pintype "passive"))
    )
    (net (code "43") (name "/PWM_M2") (class "Default")
      (node (ref "IC3") (pin "8") (pinfunction "PWM_8") (pintype "input"))
      (node (ref "MC1") (pin "4") (pinfunction "4/CAN-RX-PWM_4") (pintype "bidirectional"))
      (node (ref "R12") (pin "1") (pinfunction "1_1") (pintype "passive"))
    )
    (net (code "44") (name "/PWM_M3") (class "Default")
      (node (ref "IC4") (pin "8") (pinfunction "PWM_8") (pintype "input"))
      (node (ref "MC1") (pin "5") (pinfunction "5/PWM_5") (pintype "bidirectional"))
      (node (ref "R18") (pin "1") (pinfunction "1_1") (pintype "passive"))
    )
    (net (code "45") (name "/PWM_M4") (class "Default")
      (node (ref "IC5") (pin "8") (pinfunction "PWM_8") (pintype "input"))
      (node (ref "MC1") (pin "6") (pinfunction "6/PWM_6") (pintype "bidirectional"))
      (node (ref "R24") (pin "1") (pinfunction "1_1") (pintype "passive"))
    )
    (net (code "46") (name "/PWM_M5") (class "Default")
      (node (ref "IC7") (pin "8") (pinfunction "PWM_8") (pintype "input"))
      (node (ref "MC1") (pin "9") (pinfunction "9/RX2/PWM_9") (pintype "bidirectional"))
      (node (ref "R30") (pin "1") (pinfunction "1_1") (pintype "passive"))
    )
    (net (code "47") (name "/PWM_M6") (class "Default")
      (node (ref "IC10") (pin "8") (pinfunction "PWM_8") (pintype "input"))
      (node (ref "MC1") (pin "10") (pinfunction "10/TX2/PWM_10") (pintype "bidirectional"))
      (node (ref "R49") (pin "1") (pinfunction "1_1") (pintype "passive"))
    )
    (net (code "48") (name "/RX") (class "Default")
      (node (ref "IC6") (pin "12") (pinfunction "R1OUT_12") (pintype "output"))
      (node (ref "MC1") (pin "0") (pinfunction "0/RX1/T_0") (pintype "bidirectional"))
    )
    (net (code "49") (name "/SCL") (class "Default")
      (node (ref "IC8") (pin "22") (pinfunction "SCL_22") (pintype "input"))
      (node (ref "IC9") (pin "22") (pinfunction "SCL_22") (pintype "input"))
      (node (ref "MC1") (pin "19/A5") (pinfunction "19/A5/T/SCL0_19/A5") (pintype "bidirectional"))
      (node (ref "R32") (pin "1") (pinfunction "1_1") (pintype "passive"))
    )
    (net (code "50") (name "/SDA") (class "Default")
      (node (ref "IC8") (pin "23") (pinfunction "SDA_23") (pintype "bidirectional"))
      (node (ref "IC9") (pin "23") (pinfunction "SDA_23") (pintype "bidirectional"))
      (node (ref "MC1") (pin "18/A4") (pinfunction "18/A4/T/SDA0_18/A4") (pintype "bidirectional"))
      (node (ref "R31") (pin "1") (pinfunction "1_1") (pintype "passive"))
    )
    (net (code "51") (name "/SOL_DRV") (class "Default")
      (node (ref "LED51") (pin "C") (pinfunction "C_C") (pintype "passive"))
      (node (ref "LED52") (pin "A") (pinfunction "A_A") (pintype "passive"))
      (node (ref "MC1") (pin "23/A9") (pinfunction "23/A9/T/PWM_23/A9") (pintype "bidirectional"))
      (node (ref "Q1") (pin "1") (pinfunction "G_1") (pintype "passive"))
    )
    (net (code "52") (name "/TX") (class "Default")
      (node (ref "IC6") (pin "11") (pinfunction "T1IN_11") (pintype "input"))
      (node (ref "MC1") (pin "1") (pinfunction "1/TX1/T_1") (pintype "bidirectional"))
    )
    (net (code "53") (name "/UP1") (class "Default")
      (node (ref "M1UP") (pin "2@1") (pinfunction "KL1_2@1") (pintype "passive"))
      (node (ref "MC1") (pin "24") (pinfunction "24_24") (pintype "bidirectional"))
      (node (ref "R35") (pin "2") (pinfunction "2_2") (pintype "passive"))
    )
    (net (code "54") (name "/UP2") (class "Default")
      (node (ref "M2UP") (pin "2@1") (pinfunction "KL1_2@1") (pintype "passive"))
      (node (ref "MC1") (pin "25") (pinfunction "25/T/PWM_25") (pintype "bidirectional"))
      (node (ref "R37") (pin "2") (pinfunction "2_2") (pintype "passive"))
    )
    (net (code "55") (name "/UP3") (class "Default")
      (node (ref "M3UP") (pin "2@1") (pinfunction "KL1_2@1") (pintype "passive"))
      (node (ref "MC1") (pin "26") (pinfunction "26/A15_26") (pintype "bidirectional"))
      (node (ref "R39") (pin "2") (pinfunction "2_2") (pintype "passive"))
    )
    (net (code "56") (name "/UP4") (class "Default")
      (node (ref "M4UP") (pin "2@1") (pinfunction "KL1_2@1") (pintype "passive"))
      (node (ref "MC1") (pin "27") (pinfunction "27/A16_27") (pintype "bidirectional"))
      (node (ref "R41") (pin "2") (pinfunction "2_2") (pintype "passive"))
    )
    (net (code "57") (name "/UP5") (class "Default")
      (node (ref "M5UP") (pin "2@1") (pinfunction "KL1_2@1") (pintype "passive"))
      (node (ref "MC1") (pin "28") (pinfunction "28/A17_28") (pintype "bidirectional"))
      (node (ref "R43") (pin "2") (pinfunction "2_2") (pintype "passive"))
    )
    (net (code "58") (name "/VUSB") (class "Default")
      (node (ref "MC1") (pin "VUSB") (pinfunction "VUSB_VUSB") (pintype "power_in"))
    )
    (net (code "61") (name "GND") (class "Default")
      (node (ref "BAT1") (pin "1") (pinfunction "+_1") (pintype "power_in"))
      (node (ref "C1") (pin "-") (pinfunction "-_-") (pintype "passive"))
      (node (ref "C10") (pin "-") (pinfunction "-_-") (pintype "passive"))
      (node (ref "C11") (pin "-") (pinfunction "-_-") (pintype "passive"))
      (node (ref "C12") (pin "-") (pinfunction "-_-") (pintype "passive"))
      (node (ref "C13") (pin "-") (pinfunction "-_-") (pintype "passive"))
      (node (ref "C2") (pin "2") (pinfunction "2_2") (pintype "passive"))
      (node (ref "C3") (pin "2") (pinfunction "2_2") (pintype "passive"))
      (node (ref "C4") (pin "2") (pinfunction "2_2") (pintype "passive"))
      (node (ref "C7") (pin "2") (pinfunction "2_2") (pintype "passive"))
      (node (ref "C8") (pin "2") (pinfunction "2_2") (pintype "passive"))
      (node (ref "C9") (pin "-") (pinfunction "-_-") (pintype "passive"))
      (node (ref "IC1") (pin "18") (pinfunction "GNDB_18") (pintype "power_in"))
      (node (ref "IC1") (pin "19") (pinfunction "GNDB_19") (pintype "power_in"))
      (node (ref "IC1") (pin "20") (pinfunction "GNDB_20") (pintype "power_in"))
      (node (ref "IC1") (pin "26") (pinfunction "GNDA_26") (pintype "power_in"))
      (node (ref "IC1") (pin "27") (pinfunction "GNDA_27") (pintype "power_in"))
      (node (ref "IC1") (pin "28") (pinfunction "GNDA_28") (pintype "power_in"))
      (node (ref "IC10") (pin "18") (pinfunction "GNDB_18") (pintype "power_in"))
      (node (ref "IC10") (pin "19") (pinfunction "GNDB_19") (pintype "power_in"))
      (node (ref "IC10") (pin "20") (pinfunction "GNDB_20") (pintype "power_in"))
      (node (ref "IC10") (pin "26") (pinfunction "GNDA_26") (pintype "power_in"))
      (node (ref "IC10") (pin "27") (pinfunction "GNDA_27") (pintype "power_in"))
      (node (ref "IC10") (pin "28") (pinfunction "GNDA_28") (pintype "power_in"))
      (node (ref "IC2") (pin "4") (pinfunction "GND_4") (pintype "passive"))
      (node (ref "IC3") (pin "18") (pinfunction "GNDB_18") (pintype "power_in"))
      (node (ref "IC3") (pin "19") (pinfunction "GNDB_19") (pintype "power_in"))
      (node (ref "IC3") (pin "20") (pinfunction "GNDB_20") (pintype "power_in"))
      (node (ref "IC3") (pin "26") (pinfunction "GNDA_26") (pintype "power_in"))
      (node (ref "IC3") (pin "27") (pinfunction "GNDA_27") (pintype "power_in"))
      (node (ref "IC3") (pin "28") (pinfunction "GNDA_28") (pintype "power_in"))
      (node (ref "IC4") (pin "18") (pinfunction "GNDB_18") (pintype "power_in"))
      (node (ref "IC4") (pin "19") (pinfunction "GNDB_19") (pintype "power_in"))
      (node (ref "IC4") (pin "20") (pinfunction "GNDB_20") (pintype "power_in"))
      (node (ref "IC4") (pin "26") (pinfunction "GNDA_26") (pintype "power_in"))
      (node (ref "IC4") (pin "27") (pinfunction "GNDA_27") (pintype "power_in"))
      (node (ref "IC4") (pin "28") (pinfunction "GNDA_28") (pintype "power_in"))
      (node (ref "IC5") (pin "18") (pinfunction "GNDB_18") (pintype "power_in"))
      (node (ref "IC5") (pin "19") (pinfunction "GNDB_19") (pintype "power_in"))
      (node (ref "IC5") (pin "20") (pinfunction "GNDB_20") (pintype "power_in"))
      (node (ref "IC5") (pin "26") (pinfunction "GNDA_26") (pintype "power_in"))
      (node (ref "IC5") (pin "27") (pinfunction "GNDA_27") (pintype "power_in"))
      (node (ref "IC5") (pin "28") (pinfunction "GNDA_28") (pintype "power_in"))
      (node (ref "IC6") (pin "15") (pinfunction "GND_15") (pintype "power_in"))
      (node (ref "IC7") (pin "18") (pinfunction "GNDB_18") (pintype "power_in"))
      (node (ref "IC7") (pin "19") (pinfunction "GNDB_19") (pintype "power_in"))
      (node (ref "IC7") (pin "20") (pinfunction "GNDB_20") (pintype "power_in"))
      (node (ref "IC7") (pin "26") (pinfunction "GNDA_26") (pintype "power_in"))
      (node (ref "IC7") (pin "27") (pinfunction "GNDA_27") (pintype "power_in"))
      (node (ref "IC7") (pin "28") (pinfunction "GNDA_28") (pintype "power_in"))
      (node (ref "IC8") (pin "12") (pinfunction "VSS_12") (pintype "power_in"))
      (node (ref "IC8") (pin "2") (pinfunction "A1_2") (pintype "input"))
      (node (ref "IC8") (pin "21") (pinfunction "A0_21") (pintype "input"))
      (node (ref "IC8") (pin "3") (pinfunction "A2_3") (pintype "input"))
      (node (ref "IC9") (pin "12") (pinfunction "VSS_12") (pintype "power_in"))
      (node (ref "IC9") (pin "2") (pinfunction "A1_2") (pintype "input"))
      (node (ref "IC9") (pin "3") (pinfunction "A2_3") (pintype "input"))
      (node (ref "LED13") (pin "C") (pinfunction "C_C") (pintype "passive"))
      (node (ref "LED14") (pin "C") (pinfunction "C_C") (pintype "passive"))
      (node (ref "LED23") (pin "C") (pinfunction "C_C") (pintype "passive"))
      (node (ref "LED24") (pin "C") (pinfunction "C_C") (pintype "passive"))
      (node (ref "LED3") (pin "C") (pinfunction "C_C") (pintype "passive"))
      (node (ref "LED33") (pin "C") (pinfunction "C_C") (pintype "passive"))
      (node (ref "LED34") (pin "C") (pinfunction "C_C") (pintype "passive"))
      (node (ref "LED4") (pin "C") (pinfunction "C_C") (pintype "passive"))
      (node (ref "LED43") (pin "C") (pinfunction "C_C") (pintype "passive"))
      (node (ref "LED44") (pin "C") (pinfunction "C_C") (pintype "passive"))
      (node (ref "LED52") (pin "C") (pinfunction "C_C") (pintype "passive"))
      (node (ref "LED55") (pin "C") (pinfunction "C_C") (pintype "passive"))
      (node (ref "LED56") (pin "C") (pinfunction "C_C") (pintype "passive"))
      (node (ref "M1DN") (pin "1@1") (pinfunction "KL1_1@1") (pintype "passive"))
      (node (ref "M1UP") (pin "1@1") (pinfunction "KL1_1@1") (pintype "passive"))
      (node (ref "M2DN") (pin "1@1") (pinfunction "KL1_1@1") (pintype "passive"))
      (node (ref "M2UP") (pin "1@1") (pinfunction "KL1_1@1") (pintype "passive"))
      (node (ref "M3DN\\") (pin "1@1") (pinfunction "KL1_1@1") (pintype "passive"))
      (node (ref "M3UP") (pin "1@1") (pinfunction "KL1_1@1") (pintype "passive"))
      (node (ref "M4DN") (pin "1@1") (pinfunction "KL1_1@1") (pintype "passive"))
      (node (ref "M4UP") (pin "1@1") (pinfunction "KL1_1@1") (pintype "passive"))
      (node (ref "M5DN") (pin "1@1") (pinfunction "KL1_1@1") (pintype "passive"))
      (node (ref "M5UP") (pin "1@1") (pinfunction "KL1_1@1") (pintype "passive"))
      (node (ref "MC1") (pin "AGND") (pinfunction "AGND_AGND") (pintype "power_in"))
      (node (ref "MC1") (pin "GND") (pinfunction "GND_GND") (pintype "power_in"))
      (node (ref "MC1") (pin "GND1") (pinfunction "GND_GND1") (pintype "power_in"))
      (node (ref "MC1") (pin "GND2") (pinfunction "GND_GND2") (pintype "power_in"))
      (node (ref "Q1") (pin "2") (pinfunction "S_2") (pintype "passive"))
      (node (ref "R1") (pin "1") (pinfunction "1_1") (pintype "passive"))
      (node (ref "R13") (pin "1") (pinfunction "1_1") (pintype "passive"))
      (node (ref "R19") (pin "1") (pinfunction "1_1") (pintype "passive"))
      (node (ref "R25") (pin "1") (pinfunction "1_1") (pintype "passive"))
      (node (ref "R44") (pin "1") (pinfunction "1_1") (pintype "passive"))
      (node (ref "R7") (pin "1") (pinfunction "1_1") (pintype "passive"))
      (node (ref "TETHER") (pin "4@1") (pinfunction "KL1_4@1") (pintype "passive"))
    )
    (net (code "62") (name "Net-(BAT1--)") (class "Default")
      (node (ref "BAT1") (pin "2") (pinfunction "-_2") (pintype "power_in"))
      (node (ref "MC1") (pin "VBAT") (pinfunction "VBAT_VBAT") (pintype "power_in"))
    )
    (net (code "63") (name "Net-(IC6A-C1+)") (class "Default")
      (node (ref "C5") (pin "1") (pinfunction "1_1") (pintype "passive"))
      (node (ref "IC6") (pin "1") (pinfunction "C1+_1") (pintype "bidirectional"))
    )
    (net (code "64") (name "Net-(IC6A-C1-)") (class "Default")
      (node (ref "C5") (pin "2") (pinfunction "2_2") (pintype "passive"))
      (node (ref "IC6") (pin "3") (pinfunction "C1-_3") (pintype "bidirectional"))
    )
    (net (code "65") (name "Net-(IC6A-C2+)") (class "Default")
      (node (ref "C6") (pin "1") (pinfunction "1_1") (pintype "passive"))
      (node (ref "IC6") (pin "4") (pinfunction "C2+_4") (pintype "bidirectional"))
    )
    (net (code "66") (name "Net-(IC6A-C2-)") (class "Default")
      (node (ref "C6") (pin "2") (pinfunction "2_2") (pintype "passive"))
      (node (ref "IC6") (pin "5") (pinfunction "C2-_5") (pintype "bidirectional"))
    )
    (net (code "67") (name "Net-(IC6A-V+)") (class "Default")
      (node (ref "C8") (pin "1") (pinfunction "1_1") (pintype "passive"))
      (node (ref "IC6") (pin "2") (pinfunction "V+_2") (pintype "bidirectional"))
    )
    (net (code "68") (name "Net-(IC6A-V-)") (class "Default")
      (node (ref "C7") (pin "1") (pinfunction "1_1") (pintype "passive"))
      (node (ref "IC6") (pin "6") (pinfunction "V-_6") (pintype "bidirectional"))
    )
    (net (code "69") (name "Net-(M1A-KL1)") (class "Default")
      (node (ref "IC1") (pin "15") (pinfunction "OUTB_15") (pintype "output"))
      (node (ref "IC1") (pin "16") (pinfunction "OUTB_16") (pintype "passive"))
      (node (ref "IC1") (pin "21") (pinfunction "OUTB_21") (pintype "passive"))
      (node (ref "IC1") (pin "OUTB") (pinfunction "OUTB_OUTB") (pintype "passive"))
      (node (ref "IC1") (pin "OUTB@1") (pinfunction "OUTB_OUTB@1") (pintype "passive"))
      (node (ref "M1") (pin "1@1") (pinfunction "KL1_1@1") (pintype "passive"))
      (node (ref "M1") (pin "1@2") (pinfunction "KL2_1@2") (pintype "passive"))
    )
    (net (code "70") (name "Net-(M1B-KL1)") (class "Default")
      (node (ref "IC1") (pin "1") (pinfunction "OUTA_1") (pintype "output"))
      (node (ref "IC1") (pin "25") (pinfunction "OUTA_25") (pintype "passive"))
      (node (ref "IC1") (pin "30") (pinfunction "OUTA_30") (pintype "passive"))
      (node (ref "IC1") (pin "OUTA") (pinfunction "OUTA_OUTA") (pintype "passive"))
      (node (ref "IC1") (pin "OUTA@1") (pinfunction "OUTA_OUTA@1") (pintype "passive"))
      (node (ref "M1") (pin "2@1") (pinfunction "KL1_2@1") (pintype "passive"))
      (node (ref "M1") (pin "2@2") (pinfunction "KL2_2@2") (pintype "passive"))
    )
    (net (code "71") (name "Net-(M2A-KL1)") (class "Default")
      (node (ref "IC3") (pin "15") (pinfunction "OUTB_15") (pintype "output"))
      (node (ref "IC3") (pin "16") (pinfunction "OUTB_16") (pintype "passive"))
      (node (ref "IC3") (pin "21") (pinfunction "OUTB_21") (pintype "passive"))
      (node (ref "IC3") (pin "OUTB") (pinfunction "OUTB_OUTB") (pintype "passive"))
      (node (ref "IC3") (pin "OUTB@1") (pinfunction "OUTB_OUTB@1") (pintype "passive"))
      (node (ref "M2") (pin "1@1") (pinfunction "KL1_1@1") (pintype "passive"))
      (node (ref "M2") (pin "1@2") (pinfunction "KL2_1@2") (pintype "passive"))
    )
    (net (code "72") (name "Net-(M2B-KL1)") (class "Default")
      (node (ref "IC3") (pin "1") (pinfunction "OUTA_1") (pintype "output"))
      (node (ref "IC3") (pin "25") (pinfunction "OUTA_25") (pintype "passive"))
      (node (ref "IC3") (pin "30") (pinfunction "OUTA_30") (pintype "passive"))
      (node (ref "IC3") (pin "OUTA") (pinfunction "OUTA_OUTA") (pintype "passive"))
      (node (ref "IC3") (pin "OUTA@1") (pinfunction "OUTA_OUTA@1") (pintype "passive"))
      (node (ref "M2") (pin "2@1") (pinfunction "KL1_2@1") (pintype "passive"))
      (node (ref "M2") (pin "2@2") (pinfunction "KL2_2@2") (pintype "passive"))
    )
    (net (code "73") (name "Net-(M3A-KL1)") (class "Default")
      (node (ref "IC4") (pin "15") (pinfunction "OUTB_15") (pintype "output"))
      (node (ref "IC4") (pin "16") (pinfunction "OUTB_16") (pintype "passive"))
      (node (ref "IC4") (pin "21") (pinfunction "OUTB_21") (pintype "passive"))
      (node (ref "IC4") (pin "OUTB") (pinfunction "OUTB_OUTB") (pintype "passive"))
      (node (ref "IC4") (pin "OUTB@1") (pinfunction "OUTB_OUTB@1") (pintype "passive"))
      (node (ref "M3") (pin "1@1") (pinfunction "KL1_1@1") (pintype "passive"))
      (node (ref "M3") (pin "1@2") (pinfunction "KL2_1@2") (pintype "passive"))
    )
    (net (code "74") (name "Net-(M3B-KL1)") (class "Default")
      (node (ref "IC4") (pin "1") (pinfunction "OUTA_1") (pintype "output"))
      (node (ref "IC4") (pin "25") (pinfunction "OUTA_25") (pintype "passive"))
      (node (ref "IC4") (pin "30") (pinfunction "OUTA_30") (pintype "passive"))
      (node (ref "IC4") (pin "OUTA") (pinfunction "OUTA_OUTA") (pintype "passive"))
      (node (ref "IC4") (pin "OUTA@1") (pinfunction "OUTA_OUTA@1") (pintype "passive"))
      (node (ref "M3") (pin "2@1") (pinfunction "KL1_2@1") (pintype "passive"))
      (node (ref "M3") (pin "2@2") (pinfunction "KL2_2@2") (pintype "passive"))
    )
    (net (code "75") (name "Net-(M4A-KL1)") (class "Default")
      (node (ref "IC5") (pin "15") (pinfunction "OUTB_15") (pintype "output"))
      (node (ref "IC5") (pin "16") (pinfunction "OUTB_16") (pintype "passive"))
      (node (ref "IC5") (pin "21") (pinfunction "OUTB_21") (pintype "passive"))
      (node (ref "IC5") (pin "OUTB") (pinfunction "OUTB_OUTB") (pintype "passive"))
      (node (ref "IC5") (pin "OUTB@1") (pinfunction "OUTB_OUTB@1") (pintype "passive"))
      (node (ref "M4") (pin "1@1") (pinfunction "KL1_1@1") (pintype "passive"))
      (node (ref "M4") (pin "1@2") (pinfunction "KL2_1@2") (pintype "passive"))
    )
    (net (code "76") (name "Net-(M4B-KL1)") (class "Default")
      (node (ref "IC5") (pin "1") (pinfunction "OUTA_1") (pintype "output"))
      (node (ref "IC5") (pin "25") (pinfunction "OUTA_25") (pintype "passive"))
      (node (ref "IC5") (pin "30") (pinfunction "OUTA_30") (pintype "passive"))
      (node (ref "IC5") (pin "OUTA") (pinfunction "OUTA_OUTA") (pintype "passive"))
      (node (ref "IC5") (pin "OUTA@1") (pinfunction "OUTA_OUTA@1") (pintype "passive"))
      (node (ref "M4") (pin "2@1") (pinfunction "KL1_2@1") (pintype "passive"))
      (node (ref "M4") (pin "2@2") (pinfunction "KL2_2@2") (pintype "passive"))
    )
    (net (code "77") (name "Net-(M5A-KL1)") (class "Default")
      (node (ref "IC7") (pin "15") (pinfunction "OUTB_15") (pintype "output"))
      (node (ref "IC7") (pin "16") (pinfunction "OUTB_16") (pintype "passive"))
      (node (ref "IC7") (pin "21") (pinfunction "OUTB_21") (pintype "passive"))
      (node (ref "IC7") (pin "OUTB") (pinfunction "OUTB_OUTB") (pintype "passive"))
      (node (ref "IC7") (pin "OUTB@1") (pinfunction "OUTB_OUTB@1") (pintype "passive"))
      (node (ref "M5") (pin "1@1") (pinfunction "KL1_1@1") (pintype "passive"))
      (node (ref "M5") (pin "1@2") (pinfunction "KL2_1@2") (pintype "passive"))
    )
    (net (code "78") (name "Net-(M5B-KL1)") (class "Default")
      (node (ref "IC7") (pin "1") (pinfunction "OUTA_1") (pintype "output"))
      (node (ref "IC7") (pin "25") (pinfunction "OUTA_25") (pintype "passive"))
      (node (ref "IC7") (pin "30") (pinfunction "OUTA_30") (pintype "passive"))
      (node (ref "IC7") (pin "OUTA") (pinfunction "OUTA_OUTA") (pintype "passive"))
      (node (ref "IC7") (pin "OUTA@1") (pinfunction "OUTA_OUTA@1") (pintype "passive"))
      (node (ref "M5") (pin "2@1") (pinfunction "KL1_2@1") (pintype "passive"))
      (node (ref "M5") (pin "2@2") (pinfunction "KL2_2@2") (pintype "passive"))
    )
    (net (code "79") (name "Net-(M6A-KL1)") (class "Default")
      (node (ref "IC10") (pin "15") (pinfunction "OUTB_15") (pintype "output"))
      (node (ref "IC10") (pin "16") (pinfunction "OUTB_16") (pintype "passive"))
      (node (ref "IC10") (pin "21") (pinfunction "OUTB_21") (pintype "passive"))
      (node (ref "IC10") (pin "OUTB") (pinfunction "OUTB_OUTB") (pintype "passive"))
      (node (ref "IC10") (pin "OUTB@1") (pinfunction "OUTB_OUTB@1") (pintype "passive"))
      (node (ref "M6") (pin "1@1") (pinfunction "KL1_1@1") (pintype "passive"))
      (node (ref "M6") (pin "1@2") (pinfunction "KL2_1@2") (pintype "passive"))
    )
    (net (code "80") (name "Net-(M6B-KL1)") (class "Default")
      (node (ref "IC10") (pin "1") (pinfunction "OUTA_1") (pintype "output"))
      (node (ref "IC10") (pin "25") (pinfunction "OUTA_25") (pintype "passive"))
      (node (ref "IC10") (pin "30") (pinfunction "OUTA_30") (pintype "passive"))
      (node (ref "IC10") (pin "OUTA") (pinfunction "OUTA_OUTA") (pintype "passive"))
      (node (ref "IC10") (pin "OUTA@1") (pinfunction "OUTA_OUTA@1") (pintype "passive"))
      (node (ref "M6") (pin "2@1") (pinfunction "KL1_2@1") (pintype "passive"))
      (node (ref "M6") (pin "2@2") (pinfunction "KL2_2@2") (pintype "passive"))
    )
    (net (code "81") (name "Net-(Q1-D)") (class "Default")
      (node (ref "D1") (pin "A") (pinfunction "A_A") (pintype "passive"))
      (node (ref "Q1") (pin "3") (pinfunction "D_3") (pintype "passive"))
      (node (ref "SOLENOID") (pin "2@1") (pinfunction "KL1_2@1") (pintype "passive"))
    )
    (net (code "82") (name "VCC") (class "Default")
      (node (ref "C1") (pin "+") (pinfunction "+_+") (pintype "passive"))
      (node (ref "C10") (pin "+") (pinfunction "+_+") (pintype "passive"))
      (node (ref "C11") (pin "+") (pinfunction "+_+") (pintype "passive"))
      (node (ref "C12") (pin "+") (pinfunction "+_+") (pintype "passive"))
      (node (ref "C13") (pin "+") (pinfunction "+_+") (pintype "passive"))
      (node (ref "C2") (pin "1") (pinfunction "1_1") (pintype "passive"))
      (node (ref "C9") (pin "+") (pinfunction "+_+") (pintype "passive"))
      (node (ref "D1") (pin "C") (pinfunction "C_C") (pintype "passive"))
      (node (ref "IC1") (pin "13") (pinfunction "VCC_13") (pintype "power_in"))
      (node (ref "IC1") (pin "23") (pinfunction "VCC_23") (pintype "power_in"))
      (node (ref "IC1") (pin "3") (pinfunction "VCC_3") (pintype "power_in"))
      (node (ref "IC1") (pin "VCC") (pinfunction "VCC_VCC") (pintype "power_in"))
      (node (ref "IC1") (pin "VCC@1") (pinfunction "VCC_VCC@1") (pintype "power_in"))
      (node (ref "IC10") (pin "13") (pinfunction "VCC_13") (pintype "power_in"))
      (node (ref "IC10") (pin "23") (pinfunction "VCC_23") (pintype "power_in"))
      (node (ref "IC10") (pin "3") (pinfunction "VCC_3") (pintype "power_in"))
      (node (ref "IC10") (pin "VCC") (pinfunction "VCC_VCC") (pintype "power_in"))
      (node (ref "IC10") (pin "VCC@1") (pinfunction "VCC_VCC@1") (pintype "power_in"))
      (node (ref "IC2") (pin "1") (pinfunction "VI_1") (pintype "input"))
      (node (ref "IC3") (pin "13") (pinfunction "VCC_13") (pintype "power_in"))
      (node (ref "IC3") (pin "23") (pinfunction "VCC_23") (pintype "power_in"))
      (node (ref "IC3") (pin "3") (pinfunction "VCC_3") (pintype "power_in"))
      (node (ref "IC3") (pin "VCC") (pinfunction "VCC_VCC") (pintype "power_in"))
      (node (ref "IC3") (pin "VCC@1") (pinfunction "VCC_VCC@1") (pintype "power_in"))
      (node (ref "IC4") (pin "13") (pinfunction "VCC_13") (pintype "power_in"))
      (node (ref "IC4") (pin "23") (pinfunction "VCC_23") (pintype "power_in"))
      (node (ref "IC4") (pin "3") (pinfunction "VCC_3") (pintype "power_in"))
      (node (ref "IC4") (pin "VCC") (pinfunction "VCC_VCC") (pintype "power_in"))
      (node (ref "IC4") (pin "VCC@1") (pinfunction "VCC_VCC@1") (pintype "power_in"))
      (node (ref "IC5") (pin "13") (pinfunction "VCC_13") (pintype "power_in"))
      (node (ref "IC5") (pin "23") (pinfunction "VCC_23") (pintype "power_in"))
      (node (ref "IC5") (pin "3") (pinfunction "VCC_3") (pintype "power_in"))
      (node (ref "IC5") (pin "VCC") (pinfunction "VCC_VCC") (pintype "power_in"))
      (node (ref "IC5") (pin "VCC@1") (pinfunction "VCC_VCC@1") (pintype "power_in"))
      (node (ref "IC7") (pin "13") (pinfunction "VCC_13") (pintype "power_in"))
      (node (ref "IC7") (pin "23") (pinfunction "VCC_23") (pintype "power_in"))
      (node (ref "IC7") (pin "3") (pinfunction "VCC_3") (pintype "power_in"))
      (node (ref "IC7") (pin "VCC") (pinfunction "VCC_VCC") (pintype "power_in"))
      (node (ref "IC7") (pin "VCC@1") (pinfunction "VCC_VCC@1") (pintype "power_in"))
      (node (ref "SOLENOID") (pin "1@1") (pinfunction "KL1_1@1") (pintype "passive"))
      (node (ref "TETHER") (pin "1@1") (pinfunction "KL1_1@1") (pintype "passive"))
    )
    (net (code "83") (name "unconnected-(IC6A-R2IN-Pad8)") (class "Default")
      (node (ref "IC6") (pin "8") (pinfunction "R2IN_8") (pintype "input"))
    )
    (net (code "84") (name "unconnected-(IC6A-R2OUT-Pad9)") (class "Default")
      (node (ref "IC6") (pin "9") (pinfunction "R2OUT_9") (pintype "output"))
    )
    (net (code "85") (name "unconnected-(IC6A-T2IN-Pad10)") (class "Default")
      (node (ref "IC6") (pin "10") (pinfunction "T2IN_10") (pintype "input"))
    )
    (net (code "86") (name "unconnected-(IC6A-T2OUT-Pad7)") (class "Default")
      (node (ref "IC6") (pin "7") (pinfunction "T2OUT_7") (pintype "output"))
    )
    (net (code "87") (name "unconnected-(IC8-I{slash}O1.4-Pad17)") (class "Default")
      (node (ref "IC8") (pin "17") (pinfunction "I/O1.4_17") (pintype "bidirectional"))
    )
    (net (code "88") (name "unconnected-(IC8-I{slash}O1.5-Pad18)") (class "Default")
      (node (ref "IC8") (pin "18") (pinfunction "I/O1.5_18") (pintype "bidirectional"))
    )
    (net (code "89") (name "unconnected-(IC8-I{slash}O1.6-Pad19)") (class "Default")
      (node (ref "IC8") (pin "19") (pinfunction "I/O1.6_19") (pintype "bidirectional"))
    )
    (net (code "90") (name "unconnected-(IC8-I{slash}O1.7-Pad20)") (class "Default")
      (node (ref "IC8") (pin "20") (pinfunction "I/O1.7_20") (pintype "bidirectional"))
    )
    (net (code "91") (name "unconnected-(IC8-~{INT}-Pad1)") (class "Default")
      (node (ref "IC8") (pin "1") (pinfunction "~{INT}_1") (pintype "output"))
    )
    (net (code "92") (name "unconnected-(IC9-I{slash}O1.4-Pad17)") (class "Default")
      (node (ref "IC9") (pin "17") (pinfunction "I/O1.4_17") (pintype "bidirectional"))
    )
    (net (code "93") (name "unconnected-(IC9-I{slash}O1.5-Pad18)") (class "Default")
      (node (ref "IC9") (pin "18") (pinfunction "I/O1.5_18") (pintype "bidirectional"))
    )
    (net (code "94") (name "unconnected-(IC9-I{slash}O1.6-Pad19)") (class "Default")
      (node (ref "IC9") (pin "19") (pinfunction "I/O1.6_19") (pintype "bidirectional"))
    )
    (net (code "95") (name "unconnected-(IC9-I{slash}O1.7-Pad20)") (class "Default")
      (node (ref "IC9") (pin "20") (pinfunction "I/O1.7_20") (pintype "bidirectional"))
    )
    (net (code "96") (name "unconnected-(M1DNA-KL2-Pad1@2)") (class "Default")
      (node (ref "M1DN") (pin "1@2") (pinfunction "KL2_1@2") (pintype "passive"))
    )
    (net (code "97") (name "unconnected-(M1DNB-KL2-Pad2@2)") (class "Default")
      (node (ref "M1DN") (pin "2@2") (pinfunction "KL2_2@2") (pintype "passive"))
    )
    (net (code "98") (name "unconnected-(M1UPA-KL2-Pad1@2)") (class "Default")
      (node (ref "M1UP") (pin "1@2") (pinfunction "KL2_1@2") (pintype "passive"))
    )
    (net (code "99") (name "unconnected-(M1UPB-KL2-Pad2@2)") (class "Default")
      (node (ref "M1UP") (pin "2@2") (pinfunction "KL2_2@2") (pintype "passive"))
    )
    (net (code "100") (name "unconnected-(M2DNA-KL2-Pad1@2)") (class "Default")
      (node (ref "M2DN") (pin "1@2") (pinfunction "KL2_1@2") (pintype "passive"))
    )
    (net (code "101") (name "unconnected-(M2DNB-KL2-Pad2@2)") (class "Default")
      (node (ref "M2DN") (pin "2@2") (pinfunction "KL2_2@2") (pintype "passive"))
    )
    (net (code "102") (name "unconnected-(M2UPA-KL2-Pad1@2)") (class "Default")
      (node (ref "M2UP") (pin "1@2") (pinfunction "KL2_1@2") (pintype "passive"))
    )
    (net (code "103") (name "unconnected-(M2UPB-KL2-Pad2@2)") (class "Default")
      (node (ref "M2UP") (pin "2@2") (pinfunction "KL2_2@2") (pintype "passive"))
    )
    (net (code "104") (name "unconnected-(M3DN\\A-KL2-Pad1@2)") (class "Default")
      (node (ref "M3DN\\") (pin "1@2") (pinfunction "KL2_1@2") (pintype "passive"))
    )
    (net (code "105") (name "unconnected-(M3DN\\B-KL2-Pad2@2)") (class "Default")
      (node (ref "M3DN\\") (pin "2@2") (pinfunction "KL2_2@2") (pintype "passive"))
    )
    (net (code "106") (name "unconnected-(M3UPA-KL2-Pad1@2)") (class "Default")
      (node (ref "M3UP") (pin "1@2") (pinfunction "KL2_1@2") (pintype "passive"))
    )
    (net (code "107") (name "unconnected-(M3UPB-KL2-Pad2@2)") (class "Default")
      (node (ref "M3UP") (pin "2@2") (pinfunction "KL2_2@2") (pintype "passive"))
    )
    (net (code "108") (name "unconnected-(M4DNA-KL2-Pad1@2)") (class "Default")
      (node (ref "M4DN") (pin "1@2") (pinfunction "KL2_1@2") (pintype "passive"))
    )
    (net (code "109") (name "unconnected-(M4DNB-KL2-Pad2@2)") (class "Default")
      (node (ref "M4DN") (pin "2@2") (pinfunction "KL2_2@2") (pintype "passive"))
    )
    (net (code "110") (name "unconnected-(M4UPA-KL2-Pad1@2)") (class "Default")
      (node (ref "M4UP") (pin "1@2") (pinfunction "KL2_1@2") (pintype "passive"))
    )
    (net (code "111") (name "unconnected-(M4UPB-KL2-Pad2@2)") (class "Default")
      (node (ref "M4UP") (pin "2@2") (pinfunction "KL2_2@2") (pintype "passive"))
    )
    (net (code "112") (name "unconnected-(M5DNA-KL2-Pad1@2)") (class "Default")
      (node (ref "M5DN") (pin "1@2") (pinfunction "KL2_1@2") (pintype "passive"))
    )
    (net (code "113") (name "unconnected-(M5DNB-KL2-Pad2@2)") (class "Default")
      (node (ref "M5DN") (pin "2@2") (pinfunction "KL2_2@2") (pintype "passive"))
    )
    (net (code "114") (name "unconnected-(M5UPA-KL2-Pad1@2)") (class "Default")
      (node (ref "M5UP") (pin "1@2") (pinfunction "KL2_1@2") (pintype "passive"))
    )
    (net (code "115") (name "unconnected-(M5UPB-KL2-Pad2@2)") (class "Default")
      (node (ref "M5UP") (pin "2@2") (pinfunction "KL2_2@2") (pintype "passive"))
    )
    (net (code "116") (name "unconnected-(MC1-7{slash}RX3-Pad7)") (class "Default")
      (node (ref "MC1") (pin "7") (pinfunction "7/RX3_7") (pintype "bidirectional"))
    )
    (net (code "117") (name "unconnected-(MC1-8{slash}TX3-Pad8)") (class "Default")
      (node (ref "MC1") (pin "8") (pinfunction "8/TX3_8") (pintype "bidirectional"))
    )
    (net (code "118") (name "unconnected-(MC1-11{slash}MOSI-Pad11)") (class "Default")
      (node (ref "MC1") (pin "11") (pinfunction "11/MOSI_11") (pintype "bidirectional"))
    )
    (net (code "119") (name "unconnected-(MC1-12{slash}MISO-Pad12)") (class "Default")
      (node (ref "MC1") (pin "12") (pinfunction "12/MISO_12") (pintype "bidirectional"))
    )
    (net (code "120") (name "unconnected-(MC1-13{slash}SCK{slash}LED-Pad13)") (class "Default")
      (node (ref "MC1") (pin "13") (pinfunction "13/SCK/LED_13") (pintype "bidirectional"))
    )
    (net (code "121") (name "unconnected-(MC1-22{slash}A8{slash}T{slash}PWM-Pad22{slash}A8)") (class "Default")
      (node (ref "MC1") (pin "22/A8") (pinfunction "22/A8/T/PWM_22/A8") (pintype "bidirectional"))
    )
    (net (code "122") (name "unconnected-(MC1-A14{slash}DAC-PadRESET{slash}DAC)") (class "Default")
      (node (ref "MC1") (pin "RESET/DAC") (pinfunction "A14/DAC_RESET/DAC") (pintype "bidirectional"))
    )
    (net (code "123") (name "unconnected-(MC1-PadA10)") (class "Default")
      (node (ref "MC1") (pin "A10") (pinfunction "A10_A10") (pintype "bidirectional"))
    )
    (net (code "124") (name "unconnected-(MC1-PadA11)") (class "Default")
      (node (ref "MC1") (pin "A11") (pinfunction "A11_A11") (pintype "bidirectional"))
    )
    (net (code "125") (name "unconnected-(MC1-PadA12)") (class "Default")
      (node (ref "MC1") (pin "A12") (pinfunction "A12_A12") (pintype "bidirectional"))
    )
    (net (code "126") (name "unconnected-(MC1-PadA13)") (class "Default")
      (node (ref "MC1") (pin "A13") (pinfunction "A13_A13") (pintype "bidirectional"))
    )
    (net (code "127") (name "unconnected-(MC1-PadPGM)") (class "Default")
      (node (ref "MC1") (pin "PGM") (pinfunction "PGM_PGM") (pintype "bidirectional"))
    )
    (net (code "128") (name "unconnected-(SOLENOIDA-KL2-Pad1@2)") (class "Default")
      (node (ref "SOLENOID") (pin "1@2") (pinfunction "KL2_1@2") (pintype "passive"))
    )
    (net (code "129") (name "unconnected-(SOLENOIDB-KL2-Pad2@2)") (class "Default")
      (node (ref "SOLENOID") (pin "2@2") (pinfunction "KL2_2@2") (pintype "passive"))
    )
    (net (code "130") (name "unconnected-(TETHERA-KL2-Pad1@2)") (class "Default")
      (node (ref "TETHER") (pin "1@2") (pinfunction "KL2_1@2") (pintype "passive"))
    )
    (net (code "131") (name "unconnected-(TETHERB-KL2-Pad2@2)") (class "Default")
      (node (ref "TETHER") (pin "2@2") (pinfunction "KL2_2@2") (pintype "passive"))
    )
    (net (code "132") (name "unconnected-(TETHERC-KL2-Pad3@2)") (class "Default")
      (node (ref "TETHER") (pin "3@2") (pinfunction "KL2_3@2") (pintype "passive"))
    )
    (net (code "133") (name "unconnected-(TETHERD-KL2-Pad4@2)") (class "Default")
      (node (ref "TETHER") (pin "4@2") (pinfunction "KL2_4@2") (pintype "passive"))
    )
  )
)
